# DevKitWRM1470-r1_0.net
KiCad netlist of a schematic drawn in Altium Designer
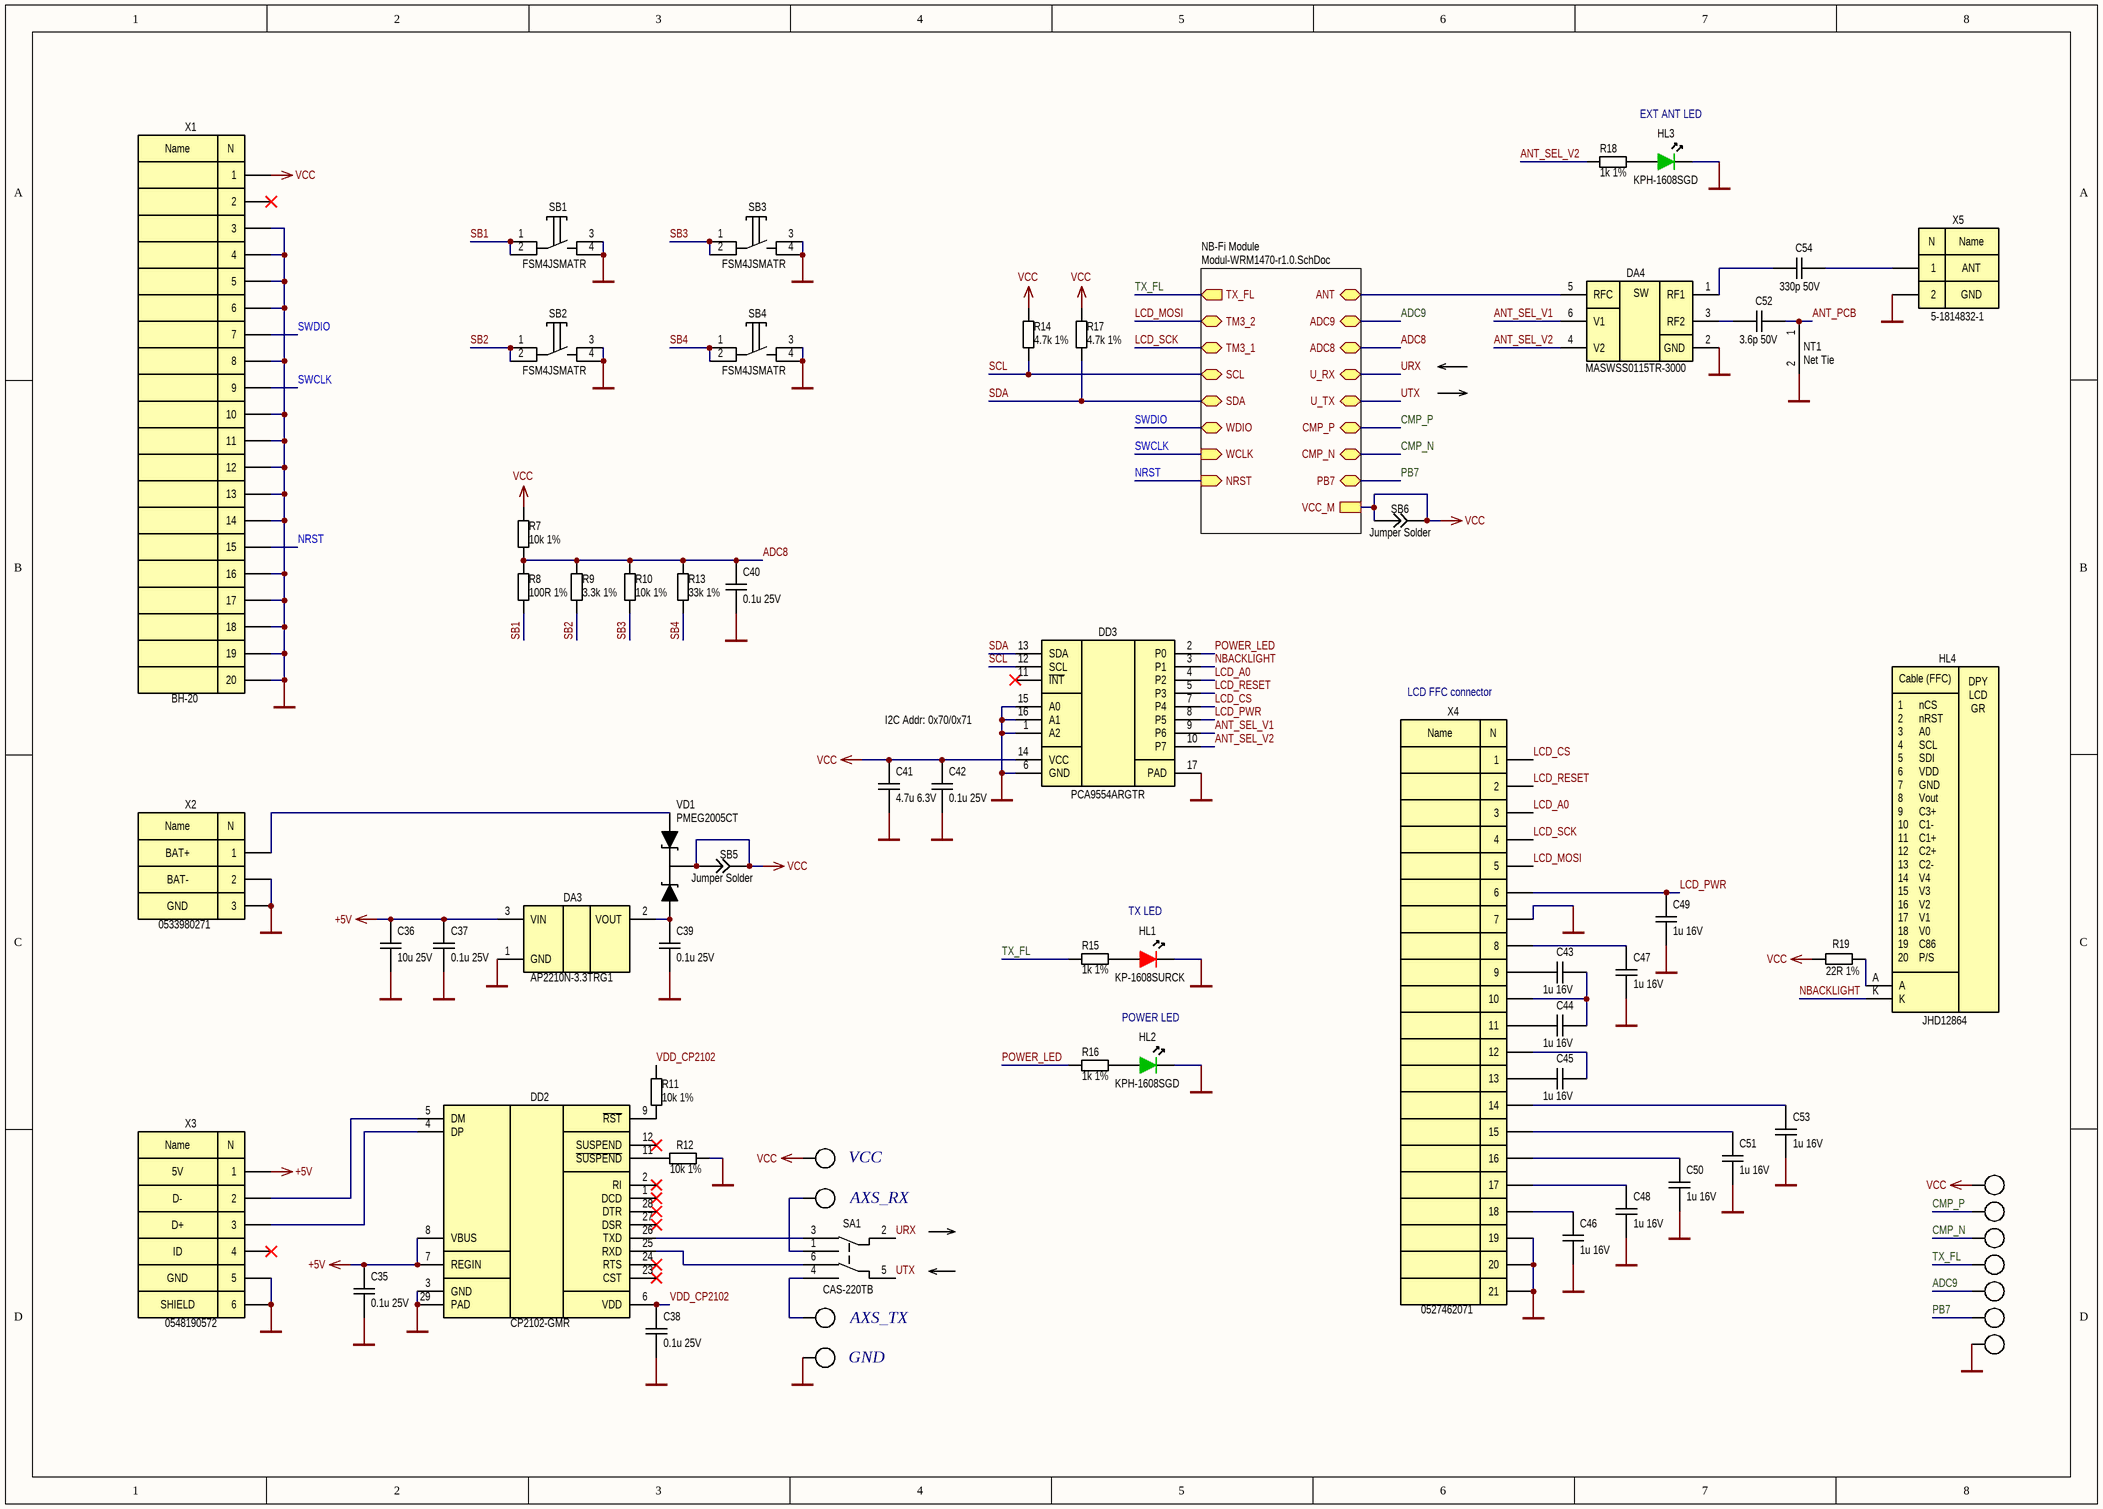
[diagram p0: DevKitWRM1470-r1.0.SchDoc]

(export (version "E")
  (design (tool "Eeschema 10.0.6"))
  (components
    (comp (ref "C35")
      (value "0.1u 25V")
      (footprint "C0402")
      (description "CAP CER 0.1UF 25V X7R 0402")
      (fields (field (name "PARTNUMBER") "CC0402KRX7R8BB104"))
      (libsource (lib "Capacitors") (part "CC0402KRX7R8BB104"))
    )
    (comp (ref "C36")
      (value "10u 25V")
      (footprint "C0805")
      (description "CAP CER 10UF 25V X5R 0805")
      (fields (field (name "PARTNUMBER") "CL21A106KAFN3NE"))
      (libsource (lib "Capacitors") (part "CL21A106KAFN3NE"))
    )
    (comp (ref "C37")
      (value "0.1u 25V")
      (footprint "C0402")
      (description "CAP CER 0.1UF 25V X7R 0402")
      (fields (field (name "PARTNUMBER") "CC0402KRX7R8BB104"))
      (libsource (lib "Capacitors") (part "CC0402KRX7R8BB104"))
    )
    (comp (ref "C38")
      (value "0.1u 25V")
      (footprint "C0402")
      (description "CAP CER 0.1UF 25V X7R 0402")
      (fields (field (name "PARTNUMBER") "CC0402KRX7R8BB104"))
      (libsource (lib "Capacitors") (part "CC0402KRX7R8BB104"))
    )
    (comp (ref "C39")
      (value "0.1u 25V")
      (footprint "C0402")
      (description "CAP CER 0.1UF 25V X7R 0402")
      (fields (field (name "PARTNUMBER") "CC0402KRX7R8BB104"))
      (libsource (lib "Capacitors") (part "CC0402KRX7R8BB104"))
    )
    (comp (ref "C40")
      (value "0.1u 25V")
      (footprint "C0402")
      (description "CAP CER 0.1UF 25V X7R 0402")
      (fields (field (name "PARTNUMBER") "CC0402KRX7R8BB104"))
      (libsource (lib "Capacitors") (part "CC0402KRX7R8BB104"))
    )
    (comp (ref "C41")
      (value "4.7u 6.3V")
      (footprint "C0402")
      (description "CAP CER 4.7UF 6.3V X5R 0402")
      (fields (field (name "PARTNUMBER") "CC0402KRX5R5BB475"))
      (libsource (lib "Capacitors") (part "CC0402KRX5R5BB475"))
    )
    (comp (ref "C42")
      (value "0.1u 25V")
      (footprint "C0402")
      (description "CAP CER 0.1UF 25V X7R 0402")
      (fields (field (name "PARTNUMBER") "CC0402KRX7R8BB104"))
      (libsource (lib "Capacitors") (part "CC0402KRX7R8BB104"))
    )
    (comp (ref "C43")
      (value "1u 16V")
      (footprint "C0402")
      (description "CAP CER 1UF 16V X5R 0402")
      (fields (field (name "PARTNUMBER") "CC0402KRX5R7BB105"))
      (libsource (lib "Capacitors") (part "CC0402KRX5R7BB105"))
    )
    (comp (ref "C44")
      (value "1u 16V")
      (footprint "C0402")
      (description "CAP CER 1UF 16V X5R 0402")
      (fields (field (name "PARTNUMBER") "CC0402KRX5R7BB105"))
      (libsource (lib "Capacitors") (part "CC0402KRX5R7BB105"))
    )
    (comp (ref "C45")
      (value "1u 16V")
      (footprint "C0402")
      (description "CAP CER 1UF 16V X5R 0402")
      (fields (field (name "PARTNUMBER") "CC0402KRX5R7BB105"))
      (libsource (lib "Capacitors") (part "CC0402KRX5R7BB105"))
    )
    (comp (ref "C46")
      (value "1u 16V")
      (footprint "C0402")
      (description "CAP CER 1UF 16V X5R 0402")
      (fields (field (name "PARTNUMBER") "CC0402KRX5R7BB105"))
      (libsource (lib "Capacitors") (part "CC0402KRX5R7BB105"))
    )
    (comp (ref "C47")
      (value "1u 16V")
      (footprint "C0402")
      (description "CAP CER 1UF 16V X5R 0402")
      (fields (field (name "PARTNUMBER") "CC0402KRX5R7BB105"))
      (libsource (lib "Capacitors") (part "CC0402KRX5R7BB105"))
    )
    (comp (ref "C48")
      (value "1u 16V")
      (footprint "C0402")
      (description "CAP CER 1UF 16V X5R 0402")
      (fields (field (name "PARTNUMBER") "CC0402KRX5R7BB105"))
      (libsource (lib "Capacitors") (part "CC0402KRX5R7BB105"))
    )
    (comp (ref "C49")
      (value "1u 16V")
      (footprint "C0402")
      (description "CAP CER 1UF 16V X5R 0402")
      (fields (field (name "PARTNUMBER") "CC0402KRX5R7BB105"))
      (libsource (lib "Capacitors") (part "CC0402KRX5R7BB105"))
    )
    (comp (ref "C50")
      (value "1u 16V")
      (footprint "C0402")
      (description "CAP CER 1UF 16V X5R 0402")
      (fields (field (name "PARTNUMBER") "CC0402KRX5R7BB105"))
      (libsource (lib "Capacitors") (part "CC0402KRX5R7BB105"))
    )
    (comp (ref "C51")
      (value "1u 16V")
      (footprint "C0402")
      (description "CAP CER 1UF 16V X5R 0402")
      (fields (field (name "PARTNUMBER") "CC0402KRX5R7BB105"))
      (libsource (lib "Capacitors") (part "CC0402KRX5R7BB105"))
    )
    (comp (ref "C52")
      (value "3.6p 50V")
      (footprint "C0402")
      (description "CAP CER 3.6PF 50V NPO 0402")
      (fields (field (name "PARTNUMBER") "CC0402BRNPO9BN3R6"))
      (libsource (lib "Capacitors") (part "CC0402BRNPO9BN3R6"))
    )
    (comp (ref "C53")
      (value "1u 16V")
      (footprint "C0402")
      (description "CAP CER 1UF 16V X5R 0402")
      (fields (field (name "PARTNUMBER") "CC0402KRX5R7BB105"))
      (libsource (lib "Capacitors") (part "CC0402KRX5R7BB105"))
    )
    (comp (ref "C54")
      (value "330p 50V")
      (footprint "C0402")
      (description "CAP CER 330PF 50V C0G/NPO 0402")
      (fields (field (name "PARTNUMBER") "CC0402JRNPO9BN331"))
      (libsource (lib "Capacitors") (part "CC0402JRNPO9BN331"))
    )
    (comp (ref "DA3")
      (value "AP2210N-3.3TRG1")
      (footprint "SOT23-3L")
      (description "IC REG LINEAR 3.3V 300MA SOT23-3")
      (libsource (lib "Integrated Circuits (ICs)") (part "AP2210N-3.3TRG1"))
    )
    (comp (ref "DA4")
      (value "MASWSS0115TR-3000")
      (footprint "SOT323-6")
      (description "RF Switch ICs DC-3.0GHz ISO 22dB IL <.3dB @ 2.4GHz")
      (libsource (lib "Integrated Circuits (ICs)") (part "MASWSS0115x"))
    )
    (comp (ref "DD2")
      (value "CP2102-GMR")
      (footprint "QFN28")
      (description "IC USB-TO-UART BRIDGE 28VQFN")
      (libsource (lib "Integrated Circuits (ICs)") (part "CP2102-GMR"))
    )
    (comp (ref "DD3")
      (value "PCA9554ARGTR")
      (footprint "QFN16")
      (description "IC I/O EXPANDER I2C 8B 16QFN")
      (libsource (lib "Integrated Circuits (ICs)") (part "PCA9554ARGTR"))
    )
    (comp (ref "HL1")
      (value "KP-1608SURCK")
      (footprint "LED0603_RED")
      (description "LED Red 0603 1.95V Forward voltage typ.")
      (libsource (lib "Optoelectronics") (part "KP-1608SURCK"))
    )
    (comp (ref "HL2")
      (value "KPH-1608SGD")
      (footprint "LED0603_GREEN")
      (description "Led Green 0603 2.2V Forward voltage typ.")
      (libsource (lib "Optoelectronics") (part "KPH-1608SGD"))
    )
    (comp (ref "HL3")
      (value "KPH-1608SGD")
      (footprint "LED0603_GREEN")
      (description "Led Green 0603 2.2V Forward voltage typ.")
      (libsource (lib "Optoelectronics") (part "KPH-1608SGD"))
    )
    (comp (ref "HL4")
      (value "JHD12864")
      (footprint "JHD12864")
      (description "Display Graphical with LED-backlight")
      (libsource (lib "Optoelectronics") (part "JHD12864"))
    )
    (comp (ref "NT1")
      (value "Net Tie")
      (footprint "NETTIE-5.0x4.0")
      (description "PCB Net Tie")
      (libsource (lib "Special") (part "NT-1"))
    )
    (comp (ref "R7")
      (value "10k 1%")
      (footprint "R0402")
      (description "RES SMD 10K OHM 1% 1/16W 0402")
      (fields (field (name "PARTNUMBER") "RC0402FR-0710KL"))
      (libsource (lib "Resistors") (part "RC0402FR-0710KL"))
    )
    (comp (ref "R8")
      (value "100R 1%")
      (footprint "R0402")
      (description "RES SMD 100 OHM 1% 1/16W 0402")
      (fields (field (name "PARTNUMBER") "RC0402FR-07100RL"))
      (libsource (lib "Resistors") (part "RC0402FR-07100RL"))
    )
    (comp (ref "R9")
      (value "3.3k 1%")
      (footprint "R0402")
      (description "RES SMD 3.3K OHM 1% 1/16W 0402")
      (fields (field (name "PARTNUMBER") "RC0402FR-073K3L"))
      (libsource (lib "Resistors") (part "RC0402FR-073K3L"))
    )
    (comp (ref "R10")
      (value "10k 1%")
      (footprint "R0402")
      (description "RES SMD 10K OHM 1% 1/16W 0402")
      (fields (field (name "PARTNUMBER") "RC0402FR-0710KL"))
      (libsource (lib "Resistors") (part "RC0402FR-0710KL"))
    )
    (comp (ref "R11")
      (value "10k 1%")
      (footprint "R0402")
      (description "RES SMD 10K OHM 1% 1/16W 0402")
      (fields (field (name "PARTNUMBER") "RC0402FR-0710KL"))
      (libsource (lib "Resistors") (part "RC0402FR-0710KL"))
    )
    (comp (ref "R12")
      (value "10k 1%")
      (footprint "R0402")
      (description "RES SMD 10K OHM 1% 1/16W 0402")
      (fields (field (name "PARTNUMBER") "RC0402FR-0710KL"))
      (libsource (lib "") (part "RC0402FR-0710KL_1"))
    )
    (comp (ref "R13")
      (value "33k 1%")
      (footprint "R0402")
      (description "RES SMD 33K OHM 1% 1/16W 0402")
      (fields (field (name "PARTNUMBER") "RC0402FR-0733KL"))
      (libsource (lib "Resistors") (part "RC0402FR-0733KL"))
    )
    (comp (ref "R14")
      (value "4.7k 1%")
      (footprint "R0402")
      (description "RES SMD 4.7K OHM 1% 1/16W 0402")
      (fields (field (name "PARTNUMBER") "RC0402FR-07470RL"))
      (libsource (lib "Resistors") (part "RC0402FR-074K7L"))
    )
    (comp (ref "R15")
      (value "1k 1%")
      (footprint "R0402")
      (description "RES SMD 1K OHM 1% 1/16W 0402")
      (fields (field (name "PARTNUMBER") "RC0402FR-071KL"))
      (libsource (lib "Resistors") (part "RC0402FR-071KL"))
    )
    (comp (ref "R16")
      (value "1k 1%")
      (footprint "R0402")
      (description "RES SMD 1K OHM 1% 1/16W 0402")
      (fields (field (name "PARTNUMBER") "RC0402FR-071KL"))
      (libsource (lib "Resistors") (part "RC0402FR-071KL"))
    )
    (comp (ref "R17")
      (value "4.7k 1%")
      (footprint "R0402")
      (description "RES SMD 4.7K OHM 1% 1/16W 0402")
      (fields (field (name "PARTNUMBER") "RC0402FR-07470RL"))
      (libsource (lib "Resistors") (part "RC0402FR-074K7L"))
    )
    (comp (ref "R18")
      (value "1k 1%")
      (footprint "R0402")
      (description "RES SMD 1K OHM 1% 1/16W 0402")
      (fields (field (name "PARTNUMBER") "RC0402FR-071KL"))
      (libsource (lib "Resistors") (part "RC0402FR-071KL"))
    )
    (comp (ref "R19")
      (value "22R 1%")
      (footprint "R0402")
      (description "RES SMD 22 OHM 1% 1/16W 0402")
      (fields (field (name "PARTNUMBER") "RC0402FR-0722RL"))
      (libsource (lib "Resistors") (part "RC0402FR-0722RL"))
    )
    (comp (ref "SA1")
      (value "CAS-220TB")
      (footprint "CAS-220")
      (description "SWITCH SLIDE DPDT 100MA 6V")
      (libsource (lib "Switches") (part "CAS-220TB"))
    )
    (comp (ref "SB1")
      (value "FSM4JSMATR")
      (footprint "FSM4JSMATR")
      (description "SWITCH TACTILE SPST-NO 0.05A 24V")
      (libsource (lib "Switches") (part "FSM4JSMATR"))
    )
    (comp (ref "SB2")
      (value "FSM4JSMATR")
      (footprint "FSM4JSMATR")
      (description "SWITCH TACTILE SPST-NO 0.05A 24V")
      (libsource (lib "Switches") (part "FSM4JSMATR"))
    )
    (comp (ref "SB3")
      (value "FSM4JSMATR")
      (footprint "FSM4JSMATR")
      (description "SWITCH TACTILE SPST-NO 0.05A 24V")
      (libsource (lib "Switches") (part "FSM4JSMATR"))
    )
    (comp (ref "SB4")
      (value "FSM4JSMATR")
      (footprint "FSM4JSMATR")
      (description "SWITCH TACTILE SPST-NO 0.05A 24V")
      (libsource (lib "Switches") (part "FSM4JSMATR"))
    )
    (comp (ref "SB5")
      (value "Jumper Solder")
      (footprint "SB0805")
      (description "Jumper Solder 0805")
      (libsource (lib "Connectors") (part "JS_0805"))
    )
    (comp (ref "SB6")
      (value "Jumper Solder")
      (footprint "SB0805")
      (description "Jumper Solder 0805")
      (libsource (lib "Connectors") (part "JS_0805"))
    )
    (comp (ref "VD1")
      (value "PMEG2005CT")
      (footprint "SOT23-3L")
      (description "DIODE ARRAY SCHOTTKY 20V SOT23")
      (libsource (lib "Discrete Semiconductor Products") (part "PMEG2005CT"))
    )
    (comp (ref "X1")
      (value "BH-20")
      (footprint "BH-20_PCB")
      (description "CONN MALE 20POS 2.54 (IDC-20MS)")
      (libsource (lib "Connectors") (part "BH-20"))
    )
    (comp (ref "X2")
      (value "0533980271")
      (footprint "0533980271_PCB")
      (description "CONN HEADER SMD 2POS 1.25MM")
      (fields (field (name "PARTNUMBER") "PLS-3"))
      (libsource (lib "Connectors") (part "0533980271"))
    )
    (comp (ref "X3")
      (value "0548190572")
      (footprint "0548190572")
      (description "CONN RCPT USB2.0 MINI B SMD R/A")
      (libsource (lib "Connectors") (part "0548190572"))
    )
    (comp (ref "X4")
      (value "0527462071")
      (footprint "0527462071_PCB")
      (description "CONN FFC BOTTOM 20POS 0.50MM R/A")
      (libsource (lib "Connectors") (part "0527462071"))
    )
    (comp (ref "X5")
      (value "5-1814832-1")
      (footprint "5-1814832-1")
      (description "CONN SMA JACK STR 50 OHM PCB")
      (libsource (lib "Connectors") (part "5-1814832-1"))
    )
    (comp (ref "XP1") (value "PLS-1") (footprint "HDR1X1") (libsource (lib "Module") (part "PLS-1")))
    (comp (ref "XP2") (value "PLS-1") (footprint "HDR1X1") (libsource (lib "Module") (part "PLS-1")))
    (comp (ref "XP3") (value "PLS-1") (footprint "HDR1X1") (libsource (lib "Module") (part "PLS-1")))
    (comp (ref "XP4") (value "PLS-1") (footprint "HDR1X1") (libsource (lib "Module") (part "PLS-1")))
    (comp (ref "XP5") (value "PLS-1") (footprint "HDR1X1") (libsource (lib "Module") (part "PLS-1")))
    (comp (ref "XP6") (value "PLS-1") (footprint "HDR1X1") (libsource (lib "Module") (part "PLS-1")))
    (comp (ref "XP7") (value "PLS-1") (footprint "HDR1X1") (libsource (lib "Module") (part "PLS-1")))
    (comp (ref "XP8") (value "PLS-1") (footprint "HDR1X1") (libsource (lib "Module") (part "PLS-1")))
    (comp (ref "XP9") (value "PLS-1") (footprint "HDR1X1") (libsource (lib "Module") (part "PLS-1")))
    (comp (ref "XP10") (value "PLS-1") (footprint "HDR1X1") (libsource (lib "Module") (part "PLS-1")))
    (comp (ref "XP11") (value "PLS-1") (footprint "HDR1X1") (libsource (lib "Module") (part "PLS-1")))
  )
  (nets
    (net (code "1") (name "+5V") (class "Default")
      (node (ref "C35") (pin "2") (pinfunction "2_2") (pintype "passive"))
      (node (ref "C36") (pin "1") (pinfunction "1_1") (pintype "passive"))
      (node (ref "C37") (pin "2") (pinfunction "2_2") (pintype "passive"))
      (node (ref "DA3") (pin "3") (pinfunction "VIN_3") (pintype "passive"))
      (node (ref "DD2") (pin "7") (pinfunction "REGIN_7") (pintype "passive"))
      (node (ref "DD2") (pin "8") (pinfunction "VBUS_8") (pintype "passive"))
      (node (ref "X3") (pin "1") (pinfunction "1_1") (pintype "passive"))
    )
    (net (code "2") (name "/ADC8") (class "Default")
      (node (ref "C40") (pin "2") (pinfunction "2_2") (pintype "passive"))
      (node (ref "R10") (pin "2") (pinfunction "2_2") (pintype "passive"))
      (node (ref "R13") (pin "2") (pinfunction "2_2") (pintype "passive"))
      (node (ref "R7") (pin "1") (pinfunction "1_1") (pintype "passive"))
      (node (ref "R8") (pin "2") (pinfunction "2_2") (pintype "passive"))
      (node (ref "R9") (pin "2") (pinfunction "2_2") (pintype "passive"))
    )
    (net (code "3") (name "/ADC9") (class "Default")
      (node (ref "XP6") (pin "1") (pinfunction "1_1") (pintype "passive"))
    )
    (net (code "4") (name "/ANT") (class "Default")
      (node (ref "DA4") (pin "5") (pinfunction "RFC_5") (pintype "passive"))
    )
    (net (code "5") (name "/ANT_PCB") (class "Default")
      (node (ref "C52") (pin "2") (pinfunction "2_2") (pintype "passive"))
      (node (ref "NT1") (pin "1") (pinfunction "1_1") (pintype "passive"))
    )
    (net (code "6") (name "/ANT_SEL_V1") (class "Default")
      (node (ref "DA4") (pin "6") (pinfunction "V1_6") (pintype "passive"))
      (node (ref "DD3") (pin "9") (pinfunction "P6_9") (pintype "passive"))
    )
    (net (code "7") (name "/ANT_SEL_V2") (class "Default")
      (node (ref "DA4") (pin "4") (pinfunction "V2_4") (pintype "passive"))
      (node (ref "DD3") (pin "10") (pinfunction "P7_10") (pintype "passive"))
      (node (ref "R18") (pin "1") (pinfunction "1_1") (pintype "passive"))
    )
    (net (code "8") (name "/CMP_N") (class "Default")
      (node (ref "XP5") (pin "1") (pinfunction "1_1") (pintype "passive"))
    )
    (net (code "9") (name "/CMP_P") (class "Default")
      (node (ref "XP9") (pin "1") (pinfunction "1_1") (pintype "passive"))
    )
    (net (code "10") (name "/LCD_A0") (class "Default")
      (node (ref "DD3") (pin "4") (pinfunction "P2_4") (pintype "passive"))
      (node (ref "X4") (pin "3") (pinfunction "3_3") (pintype "passive"))
    )
    (net (code "11") (name "/LCD_CS") (class "Default")
      (node (ref "DD3") (pin "7") (pinfunction "P4_7") (pintype "passive"))
      (node (ref "X4") (pin "1") (pinfunction "1_1") (pintype "passive"))
    )
    (net (code "12") (name "/LCD_MOSI") (class "Default")
      (node (ref "X4") (pin "5") (pinfunction "5_5") (pintype "passive"))
    )
    (net (code "13") (name "/LCD_PWR") (class "Default")
      (node (ref "C49") (pin "2") (pinfunction "2_2") (pintype "passive"))
      (node (ref "DD3") (pin "8") (pinfunction "P5_8") (pintype "passive"))
      (node (ref "X4") (pin "6") (pinfunction "6_6") (pintype "passive"))
    )
    (net (code "14") (name "/LCD_RESET") (class "Default")
      (node (ref "DD3") (pin "5") (pinfunction "P3_5") (pintype "passive"))
      (node (ref "X4") (pin "2") (pinfunction "2_2") (pintype "passive"))
    )
    (net (code "15") (name "/LCD_SCK") (class "Default")
      (node (ref "X4") (pin "4") (pinfunction "4_4") (pintype "passive"))
    )
    (net (code "16") (name "/NBACKLIGHT") (class "Default")
      (node (ref "DD3") (pin "3") (pinfunction "P1_3") (pintype "passive"))
      (node (ref "HL4") (pin "K") (pinfunction "K_K") (pintype "passive"))
    )
    (net (code "17") (name "/NRST") (class "Default")
      (node (ref "X1") (pin "15") (pinfunction "15_15") (pintype "passive"))
    )
    (net (code "18") (name "/PB7") (class "Default")
      (node (ref "XP7") (pin "1") (pinfunction "1_1") (pintype "passive"))
    )
    (net (code "19") (name "/POWER_LED") (class "Default")
      (node (ref "DD3") (pin "2") (pinfunction "P0_2") (pintype "passive"))
      (node (ref "R16") (pin "1") (pinfunction "1_1") (pintype "passive"))
    )
    (net (code "20") (name "/SB1") (class "Default")
      (node (ref "R8") (pin "1") (pinfunction "1_1") (pintype "passive"))
      (node (ref "SB1") (pin "1") (pinfunction "1_1") (pintype "passive"))
      (node (ref "SB1") (pin "2") (pinfunction "2_2") (pintype "passive"))
    )
    (net (code "21") (name "/SB2") (class "Default")
      (node (ref "R9") (pin "1") (pinfunction "1_1") (pintype "passive"))
      (node (ref "SB2") (pin "1") (pinfunction "1_1") (pintype "passive"))
      (node (ref "SB2") (pin "2") (pinfunction "2_2") (pintype "passive"))
    )
    (net (code "22") (name "/SB3") (class "Default")
      (node (ref "R10") (pin "1") (pinfunction "1_1") (pintype "passive"))
      (node (ref "SB3") (pin "1") (pinfunction "1_1") (pintype "passive"))
      (node (ref "SB3") (pin "2") (pinfunction "2_2") (pintype "passive"))
    )
    (net (code "23") (name "/SB4") (class "Default")
      (node (ref "R13") (pin "1") (pinfunction "1_1") (pintype "passive"))
      (node (ref "SB4") (pin "1") (pinfunction "1_1") (pintype "passive"))
      (node (ref "SB4") (pin "2") (pinfunction "2_2") (pintype "passive"))
    )
    (net (code "24") (name "/SCL") (class "Default")
      (node (ref "DD3") (pin "12") (pinfunction "SCL_12") (pintype "passive"))
      (node (ref "R14") (pin "1") (pinfunction "1_1") (pintype "passive"))
    )
    (net (code "25") (name "/SDA") (class "Default")
      (node (ref "DD3") (pin "13") (pinfunction "SDA_13") (pintype "passive"))
      (node (ref "R17") (pin "1") (pinfunction "1_1") (pintype "passive"))
    )
    (net (code "26") (name "/SWCLK") (class "Default")
      (node (ref "X1") (pin "9") (pinfunction "9_9") (pintype "passive"))
    )
    (net (code "27") (name "/SWDIO") (class "Default")
      (node (ref "X1") (pin "7") (pinfunction "7_7") (pintype "passive"))
    )
    (net (code "28") (name "/TX_FL") (class "Default")
      (node (ref "R15") (pin "1") (pinfunction "1_1") (pintype "passive"))
      (node (ref "XP10") (pin "1") (pinfunction "1_1") (pintype "passive"))
    )
    (net (code "29") (name "/URX") (class "Default")
      (node (ref "SA1") (pin "2") (pinfunction "6_2") (pintype "passive"))
    )
    (net (code "30") (name "/UTX") (class "Default")
      (node (ref "SA1") (pin "5") (pinfunction "5_5") (pintype "passive"))
    )
    (net (code "31") (name "/VDD_CP2102") (class "Default")
      (node (ref "C38") (pin "2") (pinfunction "2_2") (pintype "passive"))
      (node (ref "DD2") (pin "6") (pinfunction "VDD_6") (pintype "passive"))
      (node (ref "R11") (pin "2") (pinfunction "2_2") (pintype "passive"))
    )
    (net (code "32") (name "GND") (class "Default")
      (node (ref "C35") (pin "1") (pinfunction "1_1") (pintype "passive"))
      (node (ref "C36") (pin "2") (pinfunction "2_2") (pintype "passive"))
      (node (ref "C37") (pin "1") (pinfunction "1_1") (pintype "passive"))
      (node (ref "C38") (pin "1") (pinfunction "1_1") (pintype "passive"))
      (node (ref "C39") (pin "1") (pinfunction "1_1") (pintype "passive"))
      (node (ref "C40") (pin "1") (pinfunction "1_1") (pintype "passive"))
      (node (ref "C41") (pin "1") (pinfunction "1_1") (pintype "passive"))
      (node (ref "C42") (pin "1") (pinfunction "1_1") (pintype "passive"))
      (node (ref "C46") (pin "1") (pinfunction "1_1") (pintype "passive"))
      (node (ref "C47") (pin "1") (pinfunction "1_1") (pintype "passive"))
      (node (ref "C48") (pin "1") (pinfunction "1_1") (pintype "passive"))
      (node (ref "C49") (pin "1") (pinfunction "1_1") (pintype "passive"))
      (node (ref "C50") (pin "1") (pinfunction "1_1") (pintype "passive"))
      (node (ref "C51") (pin "1") (pinfunction "1_1") (pintype "passive"))
      (node (ref "C53") (pin "1") (pinfunction "1_1") (pintype "passive"))
      (node (ref "DA3") (pin "1") (pinfunction "GND_1") (pintype "passive"))
      (node (ref "DA4") (pin "2") (pinfunction "GND_2") (pintype "passive"))
      (node (ref "DD2") (pin "29") (pinfunction "PAD_29") (pintype "passive"))
      (node (ref "DD2") (pin "3") (pinfunction "GND_3") (pintype "passive"))
      (node (ref "DD3") (pin "1") (pinfunction "A2_1") (pintype "passive"))
      (node (ref "DD3") (pin "15") (pinfunction "A0_15") (pintype "passive"))
      (node (ref "DD3") (pin "16") (pinfunction "A1_16") (pintype "passive"))
      (node (ref "DD3") (pin "17") (pinfunction "PAD_17") (pintype "passive"))
      (node (ref "DD3") (pin "6") (pinfunction "GND_6") (pintype "passive"))
      (node (ref "HL1") (pin "2") (pinfunction "2_2") (pintype "passive"))
      (node (ref "HL2") (pin "2") (pinfunction "2_2") (pintype "passive"))
      (node (ref "HL3") (pin "2") (pinfunction "2_2") (pintype "passive"))
      (node (ref "NT1") (pin "2") (pinfunction "2_2") (pintype "passive"))
      (node (ref "R12") (pin "1") (pinfunction "1_1") (pintype "passive"))
      (node (ref "SB1") (pin "3") (pinfunction "3_3") (pintype "passive"))
      (node (ref "SB1") (pin "4") (pinfunction "4_4") (pintype "passive"))
      (node (ref "SB2") (pin "3") (pinfunction "3_3") (pintype "passive"))
      (node (ref "SB2") (pin "4") (pinfunction "4_4") (pintype "passive"))
      (node (ref "SB3") (pin "3") (pinfunction "3_3") (pintype "passive"))
      (node (ref "SB3") (pin "4") (pinfunction "4_4") (pintype "passive"))
      (node (ref "SB4") (pin "3") (pinfunction "3_3") (pintype "passive"))
      (node (ref "SB4") (pin "4") (pinfunction "4_4") (pintype "passive"))
      (node (ref "X1") (pin "10") (pinfunction "10_10") (pintype "passive"))
      (node (ref "X1") (pin "11") (pinfunction "11_11") (pintype "passive"))
      (node (ref "X1") (pin "12") (pinfunction "12_12") (pintype "passive"))
      (node (ref "X1") (pin "13") (pinfunction "13_13") (pintype "passive"))
      (node (ref "X1") (pin "14") (pinfunction "14_14") (pintype "passive"))
      (node (ref "X1") (pin "16") (pinfunction "16_16") (pintype "passive"))
      (node (ref "X1") (pin "17") (pinfunction "17_17") (pintype "passive"))
      (node (ref "X1") (pin "18") (pinfunction "18_18") (pintype "passive"))
      (node (ref "X1") (pin "19") (pinfunction "19_19") (pintype "passive"))
      (node (ref "X1") (pin "20") (pinfunction "20_20") (pintype "passive"))
      (node (ref "X1") (pin "3") (pinfunction "3_3") (pintype "passive"))
      (node (ref "X1") (pin "4") (pinfunction "4_4") (pintype "passive"))
      (node (ref "X1") (pin "5") (pinfunction "5_5") (pintype "passive"))
      (node (ref "X1") (pin "6") (pinfunction "6_6") (pintype "passive"))
      (node (ref "X1") (pin "8") (pinfunction "8_8") (pintype "passive"))
      (node (ref "X2") (pin "2") (pinfunction "2_2") (pintype "passive"))
      (node (ref "X2") (pin "3") (pinfunction "3_3") (pintype "passive"))
      (node (ref "X3") (pin "5") (pinfunction "5_5") (pintype "passive"))
      (node (ref "X3") (pin "6") (pinfunction "6_6") (pintype "passive"))
      (node (ref "X4") (pin "19") (pinfunction "19_19") (pintype "passive"))
      (node (ref "X4") (pin "20") (pinfunction "20_20") (pintype "passive"))
      (node (ref "X4") (pin "21") (pinfunction "21_21") (pintype "passive"))
      (node (ref "X4") (pin "7") (pinfunction "7_7") (pintype "passive"))
      (node (ref "X5") (pin "2") (pinfunction "2_2") (pintype "passive"))
      (node (ref "XP11") (pin "1") (pinfunction "1_1") (pintype "passive"))
      (node (ref "XP2") (pin "1") (pinfunction "1_1") (pintype "passive"))
    )
    (net (code "33") (name "Net-(C43-Pad1)") (class "Default")
      (node (ref "C43") (pin "1") (pinfunction "1_1") (pintype "passive"))
      (node (ref "C44") (pin "1") (pinfunction "1_1") (pintype "passive"))
      (node (ref "X4") (pin "10") (pinfunction "10_10") (pintype "passive"))
    )
    (net (code "34") (name "Net-(C43-Pad2)") (class "Default")
      (node (ref "C43") (pin "2") (pinfunction "2_2") (pintype "passive"))
      (node (ref "X4") (pin "9") (pinfunction "9_9") (pintype "passive"))
    )
    (net (code "35") (name "Net-(C44-Pad2)") (class "Default")
      (node (ref "C44") (pin "2") (pinfunction "2_2") (pintype "passive"))
      (node (ref "X4") (pin "11") (pinfunction "11_11") (pintype "passive"))
    )
    (net (code "36") (name "Net-(C45-Pad1)") (class "Default")
      (node (ref "C45") (pin "1") (pinfunction "1_1") (pintype "passive"))
      (node (ref "X4") (pin "12") (pinfunction "12_12") (pintype "passive"))
    )
    (net (code "37") (name "Net-(C45-Pad2)") (class "Default")
      (node (ref "C45") (pin "2") (pinfunction "2_2") (pintype "passive"))
      (node (ref "X4") (pin "13") (pinfunction "13_13") (pintype "passive"))
    )
    (net (code "38") (name "Net-(C46-Pad2)") (class "Default")
      (node (ref "C46") (pin "2") (pinfunction "2_2") (pintype "passive"))
      (node (ref "X4") (pin "18") (pinfunction "18_18") (pintype "passive"))
    )
    (net (code "39") (name "Net-(C47-Pad2)") (class "Default")
      (node (ref "C47") (pin "2") (pinfunction "2_2") (pintype "passive"))
      (node (ref "X4") (pin "8") (pinfunction "8_8") (pintype "passive"))
    )
    (net (code "40") (name "Net-(C48-Pad2)") (class "Default")
      (node (ref "C48") (pin "2") (pinfunction "2_2") (pintype "passive"))
      (node (ref "X4") (pin "17") (pinfunction "17_17") (pintype "passive"))
    )
    (net (code "41") (name "Net-(C50-Pad2)") (class "Default")
      (node (ref "C50") (pin "2") (pinfunction "2_2") (pintype "passive"))
      (node (ref "X4") (pin "16") (pinfunction "16_16") (pintype "passive"))
    )
    (net (code "42") (name "Net-(C51-Pad2)") (class "Default")
      (node (ref "C51") (pin "2") (pinfunction "2_2") (pintype "passive"))
      (node (ref "X4") (pin "15") (pinfunction "15_15") (pintype "passive"))
    )
    (net (code "43") (name "Net-(C53-Pad2)") (class "Default")
      (node (ref "C53") (pin "2") (pinfunction "2_2") (pintype "passive"))
      (node (ref "X4") (pin "14") (pinfunction "14_14") (pintype "passive"))
    )
    (net (code "44") (name "Net-(C54-Pad1)") (class "Default")
      (node (ref "C54") (pin "1") (pinfunction "1_1") (pintype "passive"))
      (node (ref "X5") (pin "1") (pinfunction "1_1") (pintype "passive"))
    )
    (net (code "45") (name "Net-(DA3-VOUT)") (class "Default")
      (node (ref "C39") (pin "2") (pinfunction "2_2") (pintype "passive"))
      (node (ref "DA3") (pin "2") (pinfunction "VOUT_2") (pintype "passive"))
      (node (ref "VD1") (pin "2") (pinfunction "A2_2") (pintype "passive"))
    )
    (net (code "46") (name "Net-(DA4-RF1)") (class "Default")
      (node (ref "C54") (pin "2") (pinfunction "2_2") (pintype "passive"))
      (node (ref "DA4") (pin "1") (pinfunction "RF1_1") (pintype "passive"))
    )
    (net (code "47") (name "Net-(DA4-RF2)") (class "Default")
      (node (ref "C52") (pin "1") (pinfunction "1_1") (pintype "passive"))
      (node (ref "DA4") (pin "3") (pinfunction "RF2_3") (pintype "passive"))
    )
    (net (code "48") (name "Net-(DD2-DM)") (class "Default")
      (node (ref "DD2") (pin "5") (pinfunction "DM_5") (pintype "passive"))
      (node (ref "X3") (pin "2") (pinfunction "2_2") (pintype "passive"))
    )
    (net (code "49") (name "Net-(DD2-DP)") (class "Default")
      (node (ref "DD2") (pin "4") (pinfunction "DP_4") (pintype "passive"))
      (node (ref "X3") (pin "3") (pinfunction "3_3") (pintype "passive"))
    )
    (net (code "50") (name "Net-(DD2-RXD)") (class "Default")
      (node (ref "DD2") (pin "25") (pinfunction "RXD_25") (pintype "passive"))
      (node (ref "SA1") (pin "6") (pinfunction "6_6") (pintype "passive"))
    )
    (net (code "51") (name "Net-(DD2-TXD)") (class "Default")
      (node (ref "DD2") (pin "26") (pinfunction "TXD_26") (pintype "passive"))
      (node (ref "SA1") (pin "3") (pinfunction "3_3") (pintype "passive"))
    )
    (net (code "52") (name "Net-(DD2-~{RST})") (class "Default")
      (node (ref "DD2") (pin "9") (pinfunction "~{RST}_9") (pintype "passive"))
      (node (ref "R11") (pin "1") (pinfunction "1_1") (pintype "passive"))
    )
    (net (code "53") (name "Net-(DD2-~{SUSPEND})") (class "Default")
      (node (ref "DD2") (pin "11") (pinfunction "~{SUSPEND}_11") (pintype "passive"))
      (node (ref "R12") (pin "2") (pinfunction "2_2") (pintype "passive"))
    )
    (net (code "54") (name "Net-(HL1-Pad1)") (class "Default")
      (node (ref "HL1") (pin "1") (pinfunction "1_1") (pintype "passive"))
      (node (ref "R15") (pin "2") (pinfunction "2_2") (pintype "passive"))
    )
    (net (code "55") (name "Net-(HL2-Pad1)") (class "Default")
      (node (ref "HL2") (pin "1") (pinfunction "1_1") (pintype "passive"))
      (node (ref "R16") (pin "2") (pinfunction "2_2") (pintype "passive"))
    )
    (net (code "56") (name "Net-(HL3-Pad1)") (class "Default")
      (node (ref "HL3") (pin "1") (pinfunction "1_1") (pintype "passive"))
      (node (ref "R18") (pin "2") (pinfunction "2_2") (pintype "passive"))
    )
    (net (code "57") (name "Net-(HL4-PadA)") (class "Default")
      (node (ref "HL4") (pin "A") (pinfunction "A_A") (pintype "passive"))
      (node (ref "R19") (pin "1") (pinfunction "1_1") (pintype "passive"))
    )
    (net (code "58") (name "Net-(SA1-Pad1)") (class "Default")
      (node (ref "SA1") (pin "1") (pinfunction "1_1") (pintype "passive"))
      (node (ref "XP4") (pin "1") (pinfunction "1_1") (pintype "passive"))
    )
    (net (code "59") (name "Net-(SA1-Pad4)") (class "Default")
      (node (ref "SA1") (pin "4") (pinfunction "4_4") (pintype "passive"))
      (node (ref "XP1") (pin "1") (pinfunction "1_1") (pintype "passive"))
    )
    (net (code "60") (name "Net-(VD1-A1)") (class "Default")
      (node (ref "VD1") (pin "1") (pinfunction "A1_1") (pintype "passive"))
      (node (ref "X2") (pin "1") (pinfunction "1_1") (pintype "passive"))
    )
    (net (code "61") (name "VCC") (class "Default")
      (node (ref "C41") (pin "2") (pinfunction "2_2") (pintype "passive"))
      (node (ref "C42") (pin "2") (pinfunction "2_2") (pintype "passive"))
      (node (ref "DD3") (pin "14") (pinfunction "VCC_14") (pintype "passive"))
      (node (ref "R14") (pin "2") (pinfunction "2_2") (pintype "passive"))
      (node (ref "R17") (pin "2") (pinfunction "2_2") (pintype "passive"))
      (node (ref "R19") (pin "2") (pinfunction "2_2") (pintype "passive"))
      (node (ref "R7") (pin "2") (pinfunction "2_2") (pintype "passive"))
      (node (ref "SB5") (pin "1") (pinfunction "1_1") (pintype "passive"))
      (node (ref "SB5") (pin "2") (pinfunction "2_2") (pintype "passive"))
      (node (ref "SB6") (pin "1") (pinfunction "1_1") (pintype "passive"))
      (node (ref "SB6") (pin "2") (pinfunction "2_2") (pintype "passive"))
      (node (ref "VD1") (pin "3") (pinfunction "K_3") (pintype "passive"))
      (node (ref "X1") (pin "1") (pinfunction "1_1") (pintype "passive"))
      (node (ref "XP3") (pin "1") (pinfunction "1_1") (pintype "passive"))
      (node (ref "XP8") (pin "1") (pinfunction "1_1") (pintype "passive"))
    )
    (net (code "62") (name "unconnected-(DD2-CST-Pad23)") (class "Default")
      (node (ref "DD2") (pin "23") (pinfunction "CST_23") (pintype "passive+no_connect"))
    )
    (net (code "63") (name "unconnected-(DD2-DCD-Pad1)") (class "Default")
      (node (ref "DD2") (pin "1") (pinfunction "DCD_1") (pintype "passive+no_connect"))
    )
    (net (code "64") (name "unconnected-(DD2-DSR-Pad27)") (class "Default")
      (node (ref "DD2") (pin "27") (pinfunction "DSR_27") (pintype "passive+no_connect"))
    )
    (net (code "65") (name "unconnected-(DD2-DTR-Pad28)") (class "Default")
      (node (ref "DD2") (pin "28") (pinfunction "DTR_28") (pintype "passive+no_connect"))
    )
    (net (code "66") (name "unconnected-(DD2-RI-Pad2)") (class "Default")
      (node (ref "DD2") (pin "2") (pinfunction "RI_2") (pintype "passive+no_connect"))
    )
    (net (code "67") (name "unconnected-(DD2-RTS-Pad24)") (class "Default")
      (node (ref "DD2") (pin "24") (pinfunction "RTS_24") (pintype "passive+no_connect"))
    )
    (net (code "68") (name "unconnected-(DD2-SUSPEND-Pad12)") (class "Default")
      (node (ref "DD2") (pin "12") (pinfunction "SUSPEND_12") (pintype "passive+no_connect"))
    )
    (net (code "69") (name "unconnected-(DD3-~{INT}-Pad11)") (class "Default")
      (node (ref "DD3") (pin "11") (pinfunction "~{INT}_11") (pintype "passive+no_connect"))
    )
    (net (code "70") (name "unconnected-(X1-Pad2)") (class "Default")
      (node (ref "X1") (pin "2") (pinfunction "2_2") (pintype "passive+no_connect"))
    )
    (net (code "71") (name "unconnected-(X3-Pad4)") (class "Default")
      (node (ref "X3") (pin "4") (pinfunction "4_4") (pintype "passive+no_connect"))
    )
  )
)
